# FlightControl.net
KiCad netlist of a schematic drawn in EAGLE
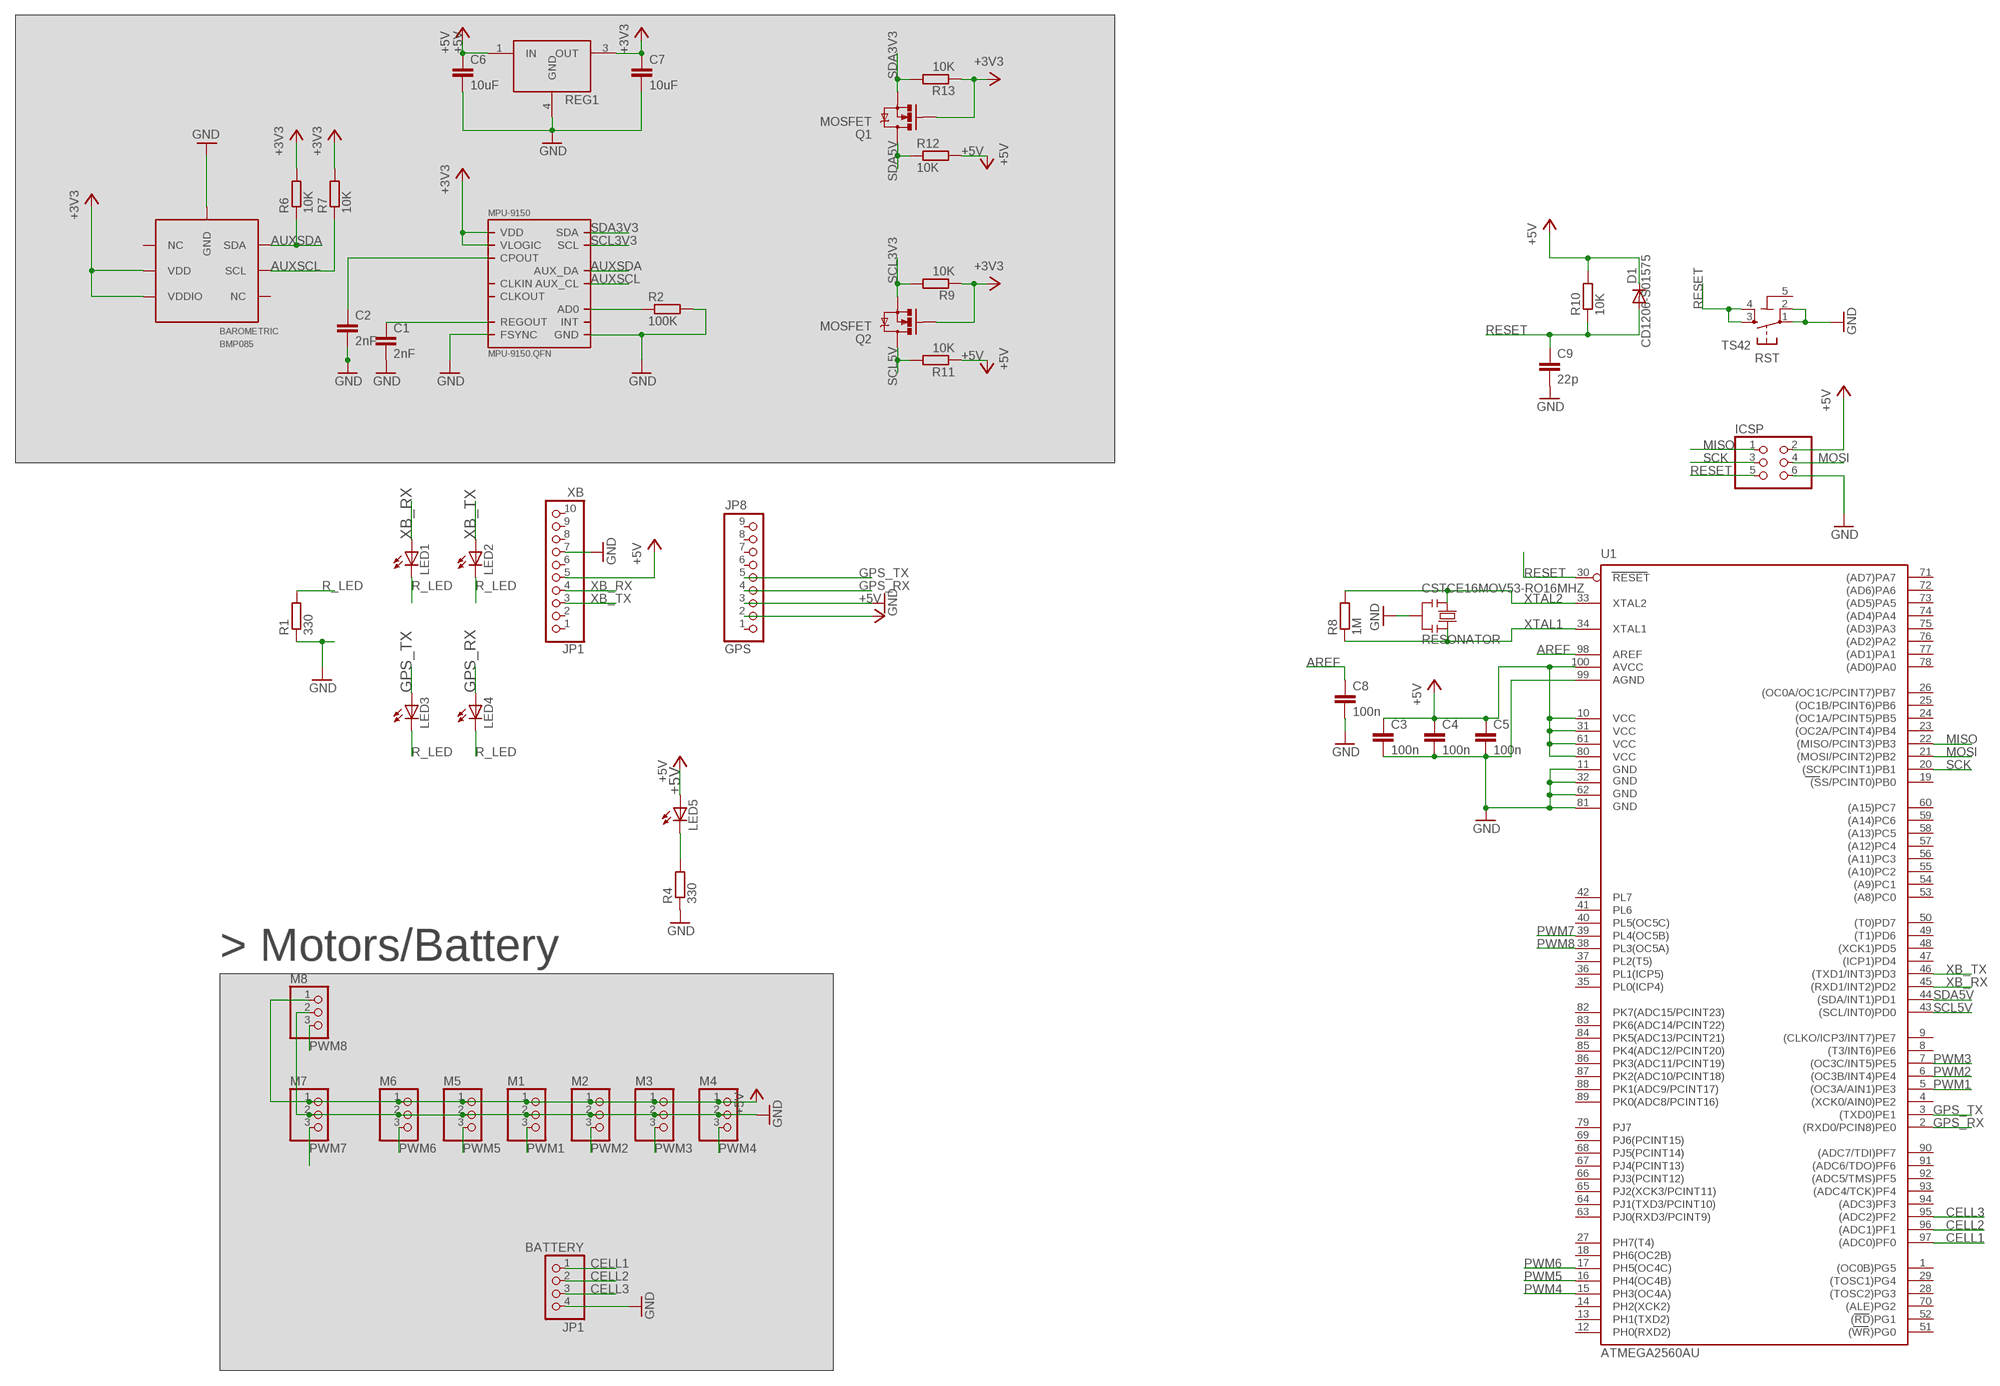
[diagram p0: schematic, sheet 1]

(export (version "E")
  (design (tool "Eeschema 10.0.6"))
  (components
    (comp (ref "BAROMETRIC")
      (value "BMP085")
      (footprint "eagle-import:7LGA")
      (libsource (lib "eagle-import") (part "BMP085"))
    )
    (comp (ref "BATTERY")
      (value "JP1")
      (footprint "eagle-import:1X04")
      (libsource (lib "eagle-import") (part "PINHD-1X4"))
    )
    (comp (ref "C1")
      (value "2nF")
      (footprint "eagle-import:C0603-ROUND")
      (libsource (lib "eagle-import") (part "C-EUC0603"))
    )
    (comp (ref "C2")
      (value "2nF")
      (footprint "eagle-import:C0603-ROUND")
      (libsource (lib "eagle-import") (part "C-EUC0603"))
    )
    (comp (ref "C3")
      (value "100n")
      (footprint "eagle-import:C0603-ROUND")
      (libsource (lib "eagle-import") (part "C-EU0603-RND"))
    )
    (comp (ref "C4")
      (value "100n")
      (footprint "eagle-import:C0603-ROUND")
      (libsource (lib "eagle-import") (part "C-EU0603-RND"))
    )
    (comp (ref "C5")
      (value "100n")
      (footprint "eagle-import:C0603-ROUND")
      (libsource (lib "eagle-import") (part "C-EU0603-RND"))
    )
    (comp (ref "C6")
      (value "10uF")
      (footprint "eagle-import:CAP-PTH-SMALLEZ")
      (libsource (lib "eagle-import") (part "CAPEZ"))
    )
    (comp (ref "C7")
      (value "10uF")
      (footprint "eagle-import:CAP-PTH-SMALLEZ")
      (libsource (lib "eagle-import") (part "CAPEZ"))
    )
    (comp (ref "C8")
      (value "100n")
      (footprint "eagle-import:C0603-ROUND")
      (libsource (lib "eagle-import") (part "C-EU0603-RND"))
    )
    (comp (ref "C9")
      (value "22p")
      (footprint "eagle-import:C0603-ROUND")
      (libsource (lib "eagle-import") (part "C-EU0603-RND"))
    )
    (comp (ref "CSTCE16MOV53-RO16MHZ")
      (value "RESONATOR")
      (footprint "eagle-import:RESONATOR")
      (libsource (lib "eagle-import") (part "RESONATORMU"))
    )
    (comp (ref "D1")
      (value "CD1206-S01575")
      (footprint "eagle-import:MINIMELF")
      (libsource (lib "eagle-import") (part "DIODE-MINIMELF"))
    )
    (comp (ref "GPS")
      (value "JP8")
      (footprint "eagle-import:1X09")
      (libsource (lib "eagle-import") (part "PINHD-1X9"))
    )
    (comp (ref "ICSP")
      (value "PINHD-2X3")
      (footprint "eagle-import:2X03")
      (libsource (lib "eagle-import") (part "PINHD-2X3"))
    )
    (comp (ref "JP1")
      (value "XB")
      (footprint "eagle-import:1X10")
      (libsource (lib "eagle-import") (part "PINHD-1X10_ARD"))
    )
    (comp (ref "LED1")
      (value "LEDCHIPLED_1206")
      (footprint "eagle-import:CHIPLED_1206")
      (libsource (lib "eagle-import") (part "LEDCHIPLED_1206"))
    )
    (comp (ref "LED2")
      (value "LEDCHIPLED_1206")
      (footprint "eagle-import:CHIPLED_1206")
      (libsource (lib "eagle-import") (part "LEDCHIPLED_1206"))
    )
    (comp (ref "LED3")
      (value "LEDCHIPLED_1206")
      (footprint "eagle-import:CHIPLED_1206")
      (libsource (lib "eagle-import") (part "LEDCHIPLED_1206"))
    )
    (comp (ref "LED4")
      (value "LEDCHIPLED_1206")
      (footprint "eagle-import:CHIPLED_1206")
      (libsource (lib "eagle-import") (part "LEDCHIPLED_1206"))
    )
    (comp (ref "LED5")
      (value "LEDCHIPLED_1206")
      (footprint "eagle-import:CHIPLED_1206")
      (libsource (lib "eagle-import") (part "LEDCHIPLED_1206"))
    )
    (comp (ref "M1")
      (value "PINHD-1X3")
      (footprint "eagle-import:1X03")
      (libsource (lib "eagle-import") (part "PINHD-1X3"))
    )
    (comp (ref "M2")
      (value "PINHD-1X3")
      (footprint "eagle-import:1X03")
      (libsource (lib "eagle-import") (part "PINHD-1X3"))
    )
    (comp (ref "M3")
      (value "PINHD-1X3")
      (footprint "eagle-import:1X03")
      (libsource (lib "eagle-import") (part "PINHD-1X3"))
    )
    (comp (ref "M4")
      (value "PINHD-1X3")
      (footprint "eagle-import:1X03")
      (libsource (lib "eagle-import") (part "PINHD-1X3"))
    )
    (comp (ref "M5")
      (value "PINHD-1X3")
      (footprint "eagle-import:1X03")
      (libsource (lib "eagle-import") (part "PINHD-1X3"))
    )
    (comp (ref "M6")
      (value "PINHD-1X3")
      (footprint "eagle-import:1X03")
      (libsource (lib "eagle-import") (part "PINHD-1X3"))
    )
    (comp (ref "M7")
      (value "PINHD-1X3")
      (footprint "eagle-import:1X03")
      (libsource (lib "eagle-import") (part "PINHD-1X3"))
    )
    (comp (ref "M8")
      (value "PINHD-1X3")
      (footprint "eagle-import:1X03")
      (libsource (lib "eagle-import") (part "PINHD-1X3"))
    )
    (comp (ref "MPU-9150")
      (value "MPU-9150.QFN")
      (footprint "eagle-import:QFN.24.4X4")
      (libsource (lib "eagle-import") (part "MPU-9150.QFN"))
    )
    (comp (ref "Q1")
      (value "MOSFET")
      (footprint "eagle-import:SOT23")
      (libsource (lib "eagle-import") (part "MOSFET-NCHANNELBSS138"))
    )
    (comp (ref "Q2")
      (value "MOSFET")
      (footprint "eagle-import:SOT23")
      (libsource (lib "eagle-import") (part "MOSFET-NCHANNELBSS138"))
    )
    (comp (ref "R1")
      (value "330")
      (footprint "eagle-import:R0603-ROUND")
      (libsource (lib "eagle-import") (part "R-EU_0603-RND"))
    )
    (comp (ref "R2")
      (value "100K")
      (footprint "eagle-import:R0603-ROUND")
      (libsource (lib "eagle-import") (part "R-EU_0603-RND"))
    )
    (comp (ref "R4")
      (value "330")
      (footprint "eagle-import:R0603-ROUND")
      (libsource (lib "eagle-import") (part "R-EU_0603-RND"))
    )
    (comp (ref "R6")
      (value "10K")
      (footprint "eagle-import:R0603-ROUND")
      (libsource (lib "eagle-import") (part "R-EU_0603-RND"))
    )
    (comp (ref "R7")
      (value "10K")
      (footprint "eagle-import:R0603-ROUND")
      (libsource (lib "eagle-import") (part "R-EU_0603-RND"))
    )
    (comp (ref "R8")
      (value "1M")
      (footprint "eagle-import:R0603-ROUND")
      (libsource (lib "eagle-import") (part "R-EU_R0603"))
    )
    (comp (ref "R9")
      (value "10K")
      (footprint "eagle-import:R0603-ROUND")
      (libsource (lib "eagle-import") (part "R-EU_R0603"))
    )
    (comp (ref "R10")
      (value "10K")
      (footprint "eagle-import:R0603-ROUND")
      (libsource (lib "eagle-import") (part "R-EU_R0603"))
    )
    (comp (ref "R11")
      (value "10K")
      (footprint "eagle-import:R0603-ROUND")
      (libsource (lib "eagle-import") (part "R-EU_R0603"))
    )
    (comp (ref "R12")
      (value "10K")
      (footprint "eagle-import:R0603-ROUND")
      (libsource (lib "eagle-import") (part "R-EU_R0603"))
    )
    (comp (ref "R13")
      (value "10K")
      (footprint "eagle-import:R0603-ROUND")
      (libsource (lib "eagle-import") (part "R-EU_R0603"))
    )
    (comp (ref "REG1")
      (value "LD39300")
      (footprint "eagle-import:DPAK")
      (libsource (lib "eagle-import") (part "LD39300"))
    )
    (comp (ref "RST")
      (value "TS42")
      (footprint "eagle-import:TS42")
      (libsource (lib "eagle-import") (part "TS42"))
    )
    (comp (ref "U1")
      (value "ATMEGA2560AU")
      (footprint "eagle-import:TQFP100")
      (libsource (lib "eagle-import") (part "ATMEGA2560AU"))
    )
  )
  (nets
    (net (code "1") (name "+3V3") (class "Default")
      (node (ref "BAROMETRIC") (pin "2") (pinfunction "VDD_2") (pintype "bidirectional"))
      (node (ref "BAROMETRIC") (pin "3") (pinfunction "VDDIO_3") (pintype "bidirectional"))
      (node (ref "C7") (pin "1") (pinfunction "1_1") (pintype "passive"))
      (node (ref "MPU-9150") (pin "13") (pinfunction "VDD_13") (pintype "bidirectional"))
      (node (ref "MPU-9150") (pin "3") (pinfunction "VDD_3") (pintype "bidirectional"))
      (node (ref "MPU-9150") (pin "8") (pinfunction "VLOGIC_8") (pintype "bidirectional"))
      (node (ref "Q1") (pin "1") (pinfunction "G_1") (pintype "passive"))
      (node (ref "Q2") (pin "1") (pinfunction "G_1") (pintype "passive"))
      (node (ref "R13") (pin "1") (pinfunction "1_1") (pintype "passive"))
      (node (ref "R6") (pin "2") (pinfunction "2_2") (pintype "passive"))
      (node (ref "R7") (pin "2") (pinfunction "2_2") (pintype "passive"))
      (node (ref "R9") (pin "1") (pinfunction "1_1") (pintype "passive"))
      (node (ref "REG1") (pin "3") (pinfunction "OUT_3") (pintype "bidirectional"))
    )
    (net (code "2") (name "+5V") (class "Default")
      (node (ref "C3") (pin "1") (pinfunction "1_1") (pintype "passive"))
      (node (ref "C4") (pin "1") (pinfunction "1_1") (pintype "passive"))
      (node (ref "C5") (pin "1") (pinfunction "1_1") (pintype "passive"))
      (node (ref "C6") (pin "1") (pinfunction "1_1") (pintype "passive"))
      (node (ref "D1") (pin "C") (pinfunction "C_C") (pintype "passive"))
      (node (ref "GPS") (pin "2") (pinfunction "2_2") (pintype "passive"))
      (node (ref "ICSP") (pin "2") (pinfunction "2_2") (pintype "passive"))
      (node (ref "JP1") (pin "5") (pinfunction "5_5") (pintype "passive"))
      (node (ref "LED5") (pin "A") (pinfunction "A_A") (pintype "passive"))
      (node (ref "M1") (pin "1") (pinfunction "1_1") (pintype "passive"))
      (node (ref "M2") (pin "1") (pinfunction "1_1") (pintype "passive"))
      (node (ref "M3") (pin "1") (pinfunction "1_1") (pintype "passive"))
      (node (ref "M4") (pin "1") (pinfunction "1_1") (pintype "passive"))
      (node (ref "M5") (pin "1") (pinfunction "1_1") (pintype "passive"))
      (node (ref "M6") (pin "1") (pinfunction "1_1") (pintype "passive"))
      (node (ref "M7") (pin "1") (pinfunction "1_1") (pintype "passive"))
      (node (ref "M8") (pin "1") (pinfunction "1_1") (pintype "passive"))
      (node (ref "R10") (pin "2") (pinfunction "2_2") (pintype "passive"))
      (node (ref "R11") (pin "1") (pinfunction "1_1") (pintype "passive"))
      (node (ref "R12") (pin "2") (pinfunction "2_2") (pintype "passive"))
      (node (ref "REG1") (pin "1") (pinfunction "IN_1") (pintype "bidirectional"))
      (node (ref "U1") (pin "10") (pinfunction "VCC_10") (pintype "power_in"))
      (node (ref "U1") (pin "100") (pinfunction "AVCC_100") (pintype "power_in"))
      (node (ref "U1") (pin "31") (pinfunction "VCC1_31") (pintype "power_in"))
      (node (ref "U1") (pin "61") (pinfunction "VCC2_61") (pintype "power_in"))
      (node (ref "U1") (pin "80") (pinfunction "VCC3_80") (pintype "power_in"))
    )
    (net (code "3") (name "/5-GND") (class "Default")
      (node (ref "RST") (pin "5") (pinfunction "5-GND_5") (pintype "power_in"))
    )
    (net (code "4") (name "/AREF") (class "Default")
      (node (ref "C8") (pin "1") (pinfunction "1_1") (pintype "passive"))
      (node (ref "U1") (pin "98") (pinfunction "AREF_98") (pintype "bidirectional"))
    )
    (net (code "5") (name "/AUXSCL") (class "Default")
      (node (ref "BAROMETRIC") (pin "5") (pinfunction "SCL_5") (pintype "bidirectional"))
      (node (ref "MPU-9150") (pin "7") (pinfunction "AUX_CL_7") (pintype "bidirectional"))
      (node (ref "R7") (pin "1") (pinfunction "1_1") (pintype "passive"))
    )
    (net (code "6") (name "/AUXSDA") (class "Default")
      (node (ref "BAROMETRIC") (pin "6") (pinfunction "SDA_6") (pintype "bidirectional"))
      (node (ref "MPU-9150") (pin "6") (pinfunction "AUX_DA_6") (pintype "bidirectional"))
      (node (ref "R6") (pin "1") (pinfunction "1_1") (pintype "passive"))
    )
    (net (code "7") (name "/CELL1") (class "Default")
      (node (ref "BATTERY") (pin "1") (pinfunction "1_1") (pintype "passive"))
      (node (ref "U1") (pin "97") (pinfunction "(ADC0)PF0_97") (pintype "bidirectional"))
    )
    (net (code "8") (name "/CELL2") (class "Default")
      (node (ref "BATTERY") (pin "2") (pinfunction "2_2") (pintype "passive"))
      (node (ref "U1") (pin "96") (pinfunction "(ADC1)PF1_96") (pintype "bidirectional"))
    )
    (net (code "9") (name "/CELL3") (class "Default")
      (node (ref "BATTERY") (pin "3") (pinfunction "3_3") (pintype "passive"))
      (node (ref "U1") (pin "95") (pinfunction "(ADC2)PF2_95") (pintype "bidirectional"))
    )
    (net (code "10") (name "/GPS_RX") (class "Default")
      (node (ref "GPS") (pin "4") (pinfunction "4_4") (pintype "passive"))
      (node (ref "LED4") (pin "A") (pinfunction "A_A") (pintype "passive"))
      (node (ref "U1") (pin "2") (pinfunction "(RXD0/PCIN8)PE0_2") (pintype "bidirectional"))
    )
    (net (code "11") (name "/GPS_TX") (class "Default")
      (node (ref "GPS") (pin "5") (pinfunction "5_5") (pintype "passive"))
      (node (ref "LED3") (pin "A") (pinfunction "A_A") (pintype "passive"))
      (node (ref "U1") (pin "3") (pinfunction "(TXD0)PE1_3") (pintype "bidirectional"))
    )
    (net (code "12") (name "/MISO") (class "Default")
      (node (ref "ICSP") (pin "1") (pinfunction "1_1") (pintype "passive"))
      (node (ref "U1") (pin "22") (pinfunction "(MISO/PCINT3)PB3_22") (pintype "bidirectional"))
    )
    (net (code "13") (name "/MOSI") (class "Default")
      (node (ref "ICSP") (pin "4") (pinfunction "4_4") (pintype "passive"))
      (node (ref "U1") (pin "21") (pinfunction "(MOSI/PCINT2)PB2_21") (pintype "bidirectional"))
    )
    (net (code "14") (name "/PWM1") (class "Default")
      (node (ref "M1") (pin "3") (pinfunction "3_3") (pintype "passive"))
      (node (ref "U1") (pin "5") (pinfunction "(OC3A/AIN1)PE3_5") (pintype "bidirectional"))
    )
    (net (code "15") (name "/PWM2") (class "Default")
      (node (ref "M2") (pin "3") (pinfunction "3_3") (pintype "passive"))
      (node (ref "U1") (pin "6") (pinfunction "(OC3B/INT4)PE4_6") (pintype "bidirectional"))
    )
    (net (code "16") (name "/PWM3") (class "Default")
      (node (ref "M3") (pin "3") (pinfunction "3_3") (pintype "passive"))
      (node (ref "U1") (pin "7") (pinfunction "(OC3C/INT5)PE5_7") (pintype "bidirectional"))
    )
    (net (code "17") (name "/PWM4") (class "Default")
      (node (ref "M4") (pin "3") (pinfunction "3_3") (pintype "passive"))
      (node (ref "U1") (pin "15") (pinfunction "PH3(OC4A)_15") (pintype "bidirectional"))
    )
    (net (code "18") (name "/PWM5") (class "Default")
      (node (ref "M5") (pin "3") (pinfunction "3_3") (pintype "passive"))
      (node (ref "U1") (pin "16") (pinfunction "PH4(OC4B)_16") (pintype "bidirectional"))
    )
    (net (code "19") (name "/PWM6") (class "Default")
      (node (ref "M6") (pin "3") (pinfunction "3_3") (pintype "passive"))
      (node (ref "U1") (pin "17") (pinfunction "PH5(OC4C)_17") (pintype "bidirectional"))
    )
    (net (code "20") (name "/PWM7") (class "Default")
      (node (ref "M7") (pin "3") (pinfunction "3_3") (pintype "passive"))
      (node (ref "U1") (pin "39") (pinfunction "PL4(OC5B)_39") (pintype "bidirectional"))
    )
    (net (code "21") (name "/PWM8") (class "Default")
      (node (ref "M8") (pin "3") (pinfunction "3_3") (pintype "passive"))
      (node (ref "U1") (pin "38") (pinfunction "PL3(OC5A)_38") (pintype "bidirectional"))
    )
    (net (code "22") (name "/RESET") (class "Default")
      (node (ref "C9") (pin "1") (pinfunction "1_1") (pintype "passive"))
      (node (ref "D1") (pin "A") (pinfunction "A_A") (pintype "passive"))
      (node (ref "ICSP") (pin "5") (pinfunction "5_5") (pintype "passive"))
      (node (ref "R10") (pin "1") (pinfunction "1_1") (pintype "passive"))
      (node (ref "RST") (pin "3") (pinfunction "3_3") (pintype "passive"))
      (node (ref "RST") (pin "4") (pinfunction "4_4") (pintype "passive"))
      (node (ref "U1") (pin "30") (pinfunction "RESET_30") (pintype "input"))
    )
    (net (code "23") (name "/R_LED") (class "Default")
      (node (ref "LED1") (pin "C") (pinfunction "C_C") (pintype "passive"))
      (node (ref "LED2") (pin "C") (pinfunction "C_C") (pintype "passive"))
      (node (ref "LED3") (pin "C") (pinfunction "C_C") (pintype "passive"))
      (node (ref "LED4") (pin "C") (pinfunction "C_C") (pintype "passive"))
      (node (ref "R1") (pin "2") (pinfunction "2_2") (pintype "passive"))
    )
    (net (code "24") (name "/SCK") (class "Default")
      (node (ref "ICSP") (pin "3") (pinfunction "3_3") (pintype "passive"))
      (node (ref "U1") (pin "20") (pinfunction "(SCK/PCINT1)PB1_20") (pintype "bidirectional"))
    )
    (net (code "25") (name "/SCL3V3") (class "Default")
      (node (ref "MPU-9150") (pin "23") (pinfunction "SCL_23") (pintype "bidirectional"))
      (node (ref "Q2") (pin "2") (pinfunction "S_2") (pintype "passive"))
      (node (ref "R9") (pin "2") (pinfunction "2_2") (pintype "passive"))
    )
    (net (code "26") (name "/SCL5V") (class "Default")
      (node (ref "Q2") (pin "3") (pinfunction "D_3") (pintype "passive"))
      (node (ref "R11") (pin "2") (pinfunction "2_2") (pintype "passive"))
      (node (ref "U1") (pin "43") (pinfunction "(SCL/INT0)PD0_43") (pintype "bidirectional"))
    )
    (net (code "27") (name "/SDA3V3") (class "Default")
      (node (ref "MPU-9150") (pin "24") (pinfunction "SDA_24") (pintype "bidirectional"))
      (node (ref "Q1") (pin "2") (pinfunction "S_2") (pintype "passive"))
      (node (ref "R13") (pin "2") (pinfunction "2_2") (pintype "passive"))
    )
    (net (code "28") (name "/SDA5V") (class "Default")
      (node (ref "Q1") (pin "3") (pinfunction "D_3") (pintype "passive"))
      (node (ref "R12") (pin "1") (pinfunction "1_1") (pintype "passive"))
      (node (ref "U1") (pin "44") (pinfunction "(SDA/INT1)PD1_44") (pintype "bidirectional"))
    )
    (net (code "29") (name "/XB_RX") (class "Default")
      (node (ref "JP1") (pin "4") (pinfunction "4_4") (pintype "passive"))
      (node (ref "LED1") (pin "A") (pinfunction "A_A") (pintype "passive"))
      (node (ref "U1") (pin "45") (pinfunction "(RXD1/INT2)PD2_45") (pintype "bidirectional"))
    )
    (net (code "30") (name "/XB_TX") (class "Default")
      (node (ref "JP1") (pin "3") (pinfunction "3_3") (pintype "passive"))
      (node (ref "LED2") (pin "A") (pinfunction "A_A") (pintype "passive"))
      (node (ref "U1") (pin "46") (pinfunction "(TXD1/INT3)PD3_46") (pintype "bidirectional"))
    )
    (net (code "31") (name "/XTAL1") (class "Default")
      (node (ref "CSTCE16MOV53-RO16MHZ") (pin "3") (pinfunction "3_3") (pintype "passive"))
      (node (ref "R8") (pin "1") (pinfunction "1_1") (pintype "passive"))
      (node (ref "U1") (pin "34") (pinfunction "XTAL1_34") (pintype "input"))
    )
    (net (code "32") (name "/XTAL2") (class "Default")
      (node (ref "CSTCE16MOV53-RO16MHZ") (pin "1") (pinfunction "1_1") (pintype "passive"))
      (node (ref "R8") (pin "2") (pinfunction "2_2") (pintype "passive"))
      (node (ref "U1") (pin "33") (pinfunction "XTAL2_33") (pintype "output"))
    )
    (net (code "33") (name "GND") (class "Default")
      (node (ref "BAROMETRIC") (pin "7") (pinfunction "GND_7") (pintype "bidirectional"))
      (node (ref "BATTERY") (pin "4") (pinfunction "4_4") (pintype "passive"))
      (node (ref "C1") (pin "2") (pinfunction "2_2") (pintype "passive"))
      (node (ref "C2") (pin "2") (pinfunction "2_2") (pintype "passive"))
      (node (ref "C3") (pin "2") (pinfunction "2_2") (pintype "passive"))
      (node (ref "C4") (pin "2") (pinfunction "2_2") (pintype "passive"))
      (node (ref "C5") (pin "2") (pinfunction "2_2") (pintype "passive"))
      (node (ref "C6") (pin "2") (pinfunction "2_2") (pintype "passive"))
      (node (ref "C7") (pin "2") (pinfunction "2_2") (pintype "passive"))
      (node (ref "C8") (pin "2") (pinfunction "2_2") (pintype "passive"))
      (node (ref "C9") (pin "2") (pinfunction "2_2") (pintype "passive"))
      (node (ref "CSTCE16MOV53-RO16MHZ") (pin "2") (pinfunction "2_2") (pintype "passive"))
      (node (ref "GPS") (pin "3") (pinfunction "3_3") (pintype "passive"))
      (node (ref "ICSP") (pin "6") (pinfunction "6_6") (pintype "passive"))
      (node (ref "JP1") (pin "7") (pinfunction "7_7") (pintype "passive"))
      (node (ref "M1") (pin "2") (pinfunction "2_2") (pintype "passive"))
      (node (ref "M2") (pin "2") (pinfunction "2_2") (pintype "passive"))
      (node (ref "M3") (pin "2") (pinfunction "2_2") (pintype "passive"))
      (node (ref "M4") (pin "2") (pinfunction "2_2") (pintype "passive"))
      (node (ref "M5") (pin "2") (pinfunction "2_2") (pintype "passive"))
      (node (ref "M6") (pin "2") (pinfunction "2_2") (pintype "passive"))
      (node (ref "M7") (pin "2") (pinfunction "2_2") (pintype "passive"))
      (node (ref "M8") (pin "2") (pinfunction "2_2") (pintype "passive"))
      (node (ref "MPU-9150") (pin "11") (pinfunction "FSYNC_11") (pintype "bidirectional"))
      (node (ref "MPU-9150") (pin "15") (pinfunction "GND_15") (pintype "bidirectional"))
      (node (ref "MPU-9150") (pin "17") (pinfunction "GND_17") (pintype "bidirectional"))
      (node (ref "MPU-9150") (pin "18") (pinfunction "GND_18") (pintype "bidirectional"))
      (node (ref "R1") (pin "1") (pinfunction "1_1") (pintype "passive"))
      (node (ref "R2") (pin "2") (pinfunction "2_2") (pintype "passive"))
      (node (ref "R4") (pin "1") (pinfunction "1_1") (pintype "passive"))
      (node (ref "REG1") (pin "4") (pinfunction "GND_4") (pintype "bidirectional"))
      (node (ref "RST") (pin "1") (pinfunction "1_1") (pintype "passive"))
      (node (ref "RST") (pin "2") (pinfunction "2_2") (pintype "passive"))
      (node (ref "U1") (pin "11") (pinfunction "GND_11") (pintype "power_in"))
      (node (ref "U1") (pin "32") (pinfunction "GND1_32") (pintype "power_in"))
      (node (ref "U1") (pin "62") (pinfunction "GND2_62") (pintype "power_in"))
      (node (ref "U1") (pin "81") (pinfunction "GND3_81") (pintype "power_in"))
      (node (ref "U1") (pin "99") (pinfunction "AGND_99") (pintype "power_in"))
    )
    (net (code "34") (name "Net-(LED5-PadC)") (class "Default")
      (node (ref "LED5") (pin "C") (pinfunction "C_C") (pintype "passive"))
      (node (ref "R4") (pin "2") (pinfunction "2_2") (pintype "passive"))
    )
    (net (code "35") (name "Net-(MPU-9150-AD0)") (class "Default")
      (node (ref "MPU-9150") (pin "9") (pinfunction "AD0_9") (pintype "bidirectional"))
      (node (ref "R2") (pin "1") (pinfunction "1_1") (pintype "passive"))
    )
    (net (code "36") (name "Net-(MPU-9150-CPOUT)") (class "Default")
      (node (ref "C2") (pin "1") (pinfunction "1_1") (pintype "passive"))
      (node (ref "MPU-9150") (pin "20") (pinfunction "CPOUT_20") (pintype "bidirectional"))
    )
    (net (code "37") (name "Net-(MPU-9150-REGOUT)") (class "Default")
      (node (ref "C1") (pin "1") (pinfunction "1_1") (pintype "passive"))
      (node (ref "MPU-9150") (pin "10") (pinfunction "REGOUT_10") (pintype "bidirectional"))
    )
    (net (code "38") (name "unconnected-(BAROMETRIC-NC-Pad1)") (class "Default")
      (node (ref "BAROMETRIC") (pin "1") (pinfunction "NC_1") (pintype "bidirectional"))
    )
    (net (code "39") (name "unconnected-(BAROMETRIC-NC-Pad4)") (class "Default")
      (node (ref "BAROMETRIC") (pin "4") (pinfunction "NC_4") (pintype "bidirectional"))
    )
    (net (code "40") (name "unconnected-(GPS-Pad1)") (class "Default")
      (node (ref "GPS") (pin "1") (pinfunction "1_1") (pintype "passive"))
    )
    (net (code "41") (name "unconnected-(GPS-Pad6)") (class "Default")
      (node (ref "GPS") (pin "6") (pinfunction "6_6") (pintype "passive"))
    )
    (net (code "42") (name "unconnected-(GPS-Pad7)") (class "Default")
      (node (ref "GPS") (pin "7") (pinfunction "7_7") (pintype "passive"))
    )
    (net (code "43") (name "unconnected-(GPS-Pad8)") (class "Default")
      (node (ref "GPS") (pin "8") (pinfunction "8_8") (pintype "passive"))
    )
    (net (code "44") (name "unconnected-(GPS-Pad9)") (class "Default")
      (node (ref "GPS") (pin "9") (pinfunction "9_9") (pintype "passive"))
    )
    (net (code "45") (name "unconnected-(JP1-Pad1)") (class "Default")
      (node (ref "JP1") (pin "1") (pinfunction "1_1") (pintype "passive"))
    )
    (net (code "46") (name "unconnected-(JP1-Pad2)") (class "Default")
      (node (ref "JP1") (pin "2") (pinfunction "2_2") (pintype "passive"))
    )
    (net (code "47") (name "unconnected-(JP1-Pad6)") (class "Default")
      (node (ref "JP1") (pin "6") (pinfunction "6_6") (pintype "passive"))
    )
    (net (code "48") (name "unconnected-(JP1-Pad8)") (class "Default")
      (node (ref "JP1") (pin "8") (pinfunction "8_8") (pintype "passive"))
    )
    (net (code "49") (name "unconnected-(JP1-Pad9)") (class "Default")
      (node (ref "JP1") (pin "9") (pinfunction "9_9") (pintype "passive"))
    )
    (net (code "50") (name "unconnected-(JP1-Pad10)") (class "Default")
      (node (ref "JP1") (pin "10") (pinfunction "10_10") (pintype "passive"))
    )
    (net (code "51") (name "unconnected-(MPU-9150-CLKIN-Pad1)") (class "Default")
      (node (ref "MPU-9150") (pin "1") (pinfunction "CLKIN_1") (pintype "bidirectional"))
    )
    (net (code "52") (name "unconnected-(MPU-9150-CLKOUT-Pad22)") (class "Default")
      (node (ref "MPU-9150") (pin "22") (pinfunction "CLKOUT_22") (pintype "bidirectional"))
    )
    (net (code "53") (name "unconnected-(MPU-9150-INT-Pad12)") (class "Default")
      (node (ref "MPU-9150") (pin "12") (pinfunction "INT_12") (pintype "bidirectional"))
    )
    (net (code "54") (name "unconnected-(U1-(A8)PC0-Pad53)") (class "Default")
      (node (ref "U1") (pin "53") (pinfunction "(A8)PC0_53") (pintype "bidirectional"))
    )
    (net (code "55") (name "unconnected-(U1-(A9)PC1-Pad54)") (class "Default")
      (node (ref "U1") (pin "54") (pinfunction "(A9)PC1_54") (pintype "bidirectional"))
    )
    (net (code "56") (name "unconnected-(U1-(A10)PC2-Pad55)") (class "Default")
      (node (ref "U1") (pin "55") (pinfunction "(A10)PC2_55") (pintype "bidirectional"))
    )
    (net (code "57") (name "unconnected-(U1-(A11)PC3-Pad56)") (class "Default")
      (node (ref "U1") (pin "56") (pinfunction "(A11)PC3_56") (pintype "bidirectional"))
    )
    (net (code "58") (name "unconnected-(U1-(A12)PC4-Pad57)") (class "Default")
      (node (ref "U1") (pin "57") (pinfunction "(A12)PC4_57") (pintype "bidirectional"))
    )
    (net (code "59") (name "unconnected-(U1-(A13)PC5-Pad58)") (class "Default")
      (node (ref "U1") (pin "58") (pinfunction "(A13)PC5_58") (pintype "bidirectional"))
    )
    (net (code "60") (name "unconnected-(U1-(A14)PC6-Pad59)") (class "Default")
      (node (ref "U1") (pin "59") (pinfunction "(A14)PC6_59") (pintype "bidirectional"))
    )
    (net (code "61") (name "unconnected-(U1-(A15)PC7-Pad60)") (class "Default")
      (node (ref "U1") (pin "60") (pinfunction "(A15)PC7_60") (pintype "bidirectional"))
    )
    (net (code "62") (name "unconnected-(U1-(AD0)PA0-Pad78)") (class "Default")
      (node (ref "U1") (pin "78") (pinfunction "(AD0)PA0_78") (pintype "bidirectional"))
    )
    (net (code "63") (name "unconnected-(U1-(AD1)PA1-Pad77)") (class "Default")
      (node (ref "U1") (pin "77") (pinfunction "(AD1)PA1_77") (pintype "bidirectional"))
    )
    (net (code "64") (name "unconnected-(U1-(AD2)PA2-Pad76)") (class "Default")
      (node (ref "U1") (pin "76") (pinfunction "(AD2)PA2_76") (pintype "bidirectional"))
    )
    (net (code "65") (name "unconnected-(U1-(AD3)PA3-Pad75)") (class "Default")
      (node (ref "U1") (pin "75") (pinfunction "(AD3)PA3_75") (pintype "bidirectional"))
    )
    (net (code "66") (name "unconnected-(U1-(AD4)PA4-Pad74)") (class "Default")
      (node (ref "U1") (pin "74") (pinfunction "(AD4)PA4_74") (pintype "bidirectional"))
    )
    (net (code "67") (name "unconnected-(U1-(AD5)PA5-Pad73)") (class "Default")
      (node (ref "U1") (pin "73") (pinfunction "(AD5)PA5_73") (pintype "bidirectional"))
    )
    (net (code "68") (name "unconnected-(U1-(AD6)PA6-Pad72)") (class "Default")
      (node (ref "U1") (pin "72") (pinfunction "(AD6)PA6_72") (pintype "bidirectional"))
    )
    (net (code "69") (name "unconnected-(U1-(AD7)PA7-Pad71)") (class "Default")
      (node (ref "U1") (pin "71") (pinfunction "(AD7)PA7_71") (pintype "bidirectional"))
    )
    (net (code "70") (name "unconnected-(U1-(ADC3)PF3-Pad94)") (class "Default")
      (node (ref "U1") (pin "94") (pinfunction "(ADC3)PF3_94") (pintype "bidirectional"))
    )
    (net (code "71") (name "unconnected-(U1-(ADC4{slash}TCK)PF4-Pad93)") (class "Default")
      (node (ref "U1") (pin "93") (pinfunction "(ADC4/TCK)PF4_93") (pintype "bidirectional"))
    )
    (net (code "72") (name "unconnected-(U1-(ADC5{slash}TMS)PF5-Pad92)") (class "Default")
      (node (ref "U1") (pin "92") (pinfunction "(ADC5/TMS)PF5_92") (pintype "bidirectional"))
    )
    (net (code "73") (name "unconnected-(U1-(ADC6{slash}TDO)PF6-Pad91)") (class "Default")
      (node (ref "U1") (pin "91") (pinfunction "(ADC6/TDO)PF6_91") (pintype "bidirectional"))
    )
    (net (code "74") (name "unconnected-(U1-(ADC7{slash}TDI)PF7-Pad90)") (class "Default")
      (node (ref "U1") (pin "90") (pinfunction "(ADC7/TDI)PF7_90") (pintype "bidirectional"))
    )
    (net (code "75") (name "unconnected-(U1-(ALE)PG2-Pad70)") (class "Default")
      (node (ref "U1") (pin "70") (pinfunction "(ALE)PG2_70") (pintype "bidirectional"))
    )
    (net (code "76") (name "unconnected-(U1-(CLKO{slash}ICP3{slash}INT7)PE7-Pad9)") (class "Default")
      (node (ref "U1") (pin "9") (pinfunction "(CLKO/ICP3/INT7)PE7_9") (pintype "bidirectional"))
    )
    (net (code "77") (name "unconnected-(U1-(ICP1)PD4-Pad47)") (class "Default")
      (node (ref "U1") (pin "47") (pinfunction "(ICP1)PD4_47") (pintype "bidirectional"))
    )
    (net (code "78") (name "unconnected-(U1-(OC0A{slash}OC1C{slash}PCINT7)PB7-Pad26)") (class "Default")
      (node (ref "U1") (pin "26") (pinfunction "(OC0A/OC1C/PCINT7)PB7_26") (pintype "bidirectional"))
    )
    (net (code "79") (name "unconnected-(U1-(OC0B)PG5-Pad1)") (class "Default")
      (node (ref "U1") (pin "1") (pinfunction "(OC0B)PG5_1") (pintype "bidirectional"))
    )
    (net (code "80") (name "unconnected-(U1-(OC1A{slash}PCINT5)PB5-Pad24)") (class "Default")
      (node (ref "U1") (pin "24") (pinfunction "(OC1A/PCINT5)PB5_24") (pintype "bidirectional"))
    )
    (net (code "81") (name "unconnected-(U1-(OC1B{slash}PCINT6)PB6-Pad25)") (class "Default")
      (node (ref "U1") (pin "25") (pinfunction "(OC1B/PCINT6)PB6_25") (pintype "bidirectional"))
    )
    (net (code "82") (name "unconnected-(U1-(OC2A{slash}PCINT4)PB4-Pad23)") (class "Default")
      (node (ref "U1") (pin "23") (pinfunction "(OC2A/PCINT4)PB4_23") (pintype "bidirectional"))
    )
    (net (code "83") (name "unconnected-(U1-(RD)PG1-Pad52)") (class "Default")
      (node (ref "U1") (pin "52") (pinfunction "(RD)PG1_52") (pintype "bidirectional"))
    )
    (net (code "84") (name "unconnected-(U1-(SS{slash}PCINT0)PB0-Pad19)") (class "Default")
      (node (ref "U1") (pin "19") (pinfunction "(SS/PCINT0)PB0_19") (pintype "bidirectional"))
    )
    (net (code "85") (name "unconnected-(U1-(T0)PD7-Pad50)") (class "Default")
      (node (ref "U1") (pin "50") (pinfunction "(T0)PD7_50") (pintype "bidirectional"))
    )
    (net (code "86") (name "unconnected-(U1-(T1)PD6-Pad49)") (class "Default")
      (node (ref "U1") (pin "49") (pinfunction "(T1)PD6_49") (pintype "bidirectional"))
    )
    (net (code "87") (name "unconnected-(U1-(T3{slash}INT6)PE6-Pad8)") (class "Default")
      (node (ref "U1") (pin "8") (pinfunction "(T3/INT6)PE6_8") (pintype "bidirectional"))
    )
    (net (code "88") (name "unconnected-(U1-(TOSC1)PG4-Pad29)") (class "Default")
      (node (ref "U1") (pin "29") (pinfunction "(TOSC1)PG4_29") (pintype "bidirectional"))
    )
    (net (code "89") (name "unconnected-(U1-(TOSC2)PG3-Pad28)") (class "Default")
      (node (ref "U1") (pin "28") (pinfunction "(TOSC2)PG3_28") (pintype "bidirectional"))
    )
    (net (code "90") (name "unconnected-(U1-(WR)PG0-Pad51)") (class "Default")
      (node (ref "U1") (pin "51") (pinfunction "(WR)PG0_51") (pintype "bidirectional"))
    )
    (net (code "91") (name "unconnected-(U1-(XCK0{slash}AIN0)PE2-Pad4)") (class "Default")
      (node (ref "U1") (pin "4") (pinfunction "(XCK0/AIN0)PE2_4") (pintype "bidirectional"))
    )
    (net (code "92") (name "unconnected-(U1-(XCK1)PD5-Pad48)") (class "Default")
      (node (ref "U1") (pin "48") (pinfunction "(XCK1)PD5_48") (pintype "bidirectional"))
    )
    (net (code "93") (name "unconnected-(U1-PH0(RXD2)-Pad12)") (class "Default")
      (node (ref "U1") (pin "12") (pinfunction "PH0(RXD2)_12") (pintype "bidirectional"))
    )
    (net (code "94") (name "unconnected-(U1-PH1(TXD2)-Pad13)") (class "Default")
      (node (ref "U1") (pin "13") (pinfunction "PH1(TXD2)_13") (pintype "bidirectional"))
    )
    (net (code "95") (name "unconnected-(U1-PH2(XCK2)-Pad14)") (class "Default")
      (node (ref "U1") (pin "14") (pinfunction "PH2(XCK2)_14") (pintype "bidirectional"))
    )
    (net (code "96") (name "unconnected-(U1-PH6(OC2B)-Pad18)") (class "Default")
      (node (ref "U1") (pin "18") (pinfunction "PH6(OC2B)_18") (pintype "bidirectional"))
    )
    (net (code "97") (name "unconnected-(U1-PH7(T4)-Pad27)") (class "Default")
      (node (ref "U1") (pin "27") (pinfunction "PH7(T4)_27") (pintype "bidirectional"))
    )
    (net (code "98") (name "unconnected-(U1-PJ0(RXD3{slash}PCINT9)-Pad63)") (class "Default")
      (node (ref "U1") (pin "63") (pinfunction "PJ0(RXD3/PCINT9)_63") (pintype "bidirectional"))
    )
    (net (code "99") (name "unconnected-(U1-PJ1(TXD3{slash}PCINT10)-Pad64)") (class "Default")
      (node (ref "U1") (pin "64") (pinfunction "PJ1(TXD3/PCINT10)_64") (pintype "bidirectional"))
    )
    (net (code "100") (name "unconnected-(U1-PJ2(XCK3{slash}PCINT11)-Pad65)") (class "Default")
      (node (ref "U1") (pin "65") (pinfunction "PJ2(XCK3/PCINT11)_65") (pintype "bidirectional"))
    )
    (net (code "101") (name "unconnected-(U1-PJ3(PCINT12)-Pad66)") (class "Default")
      (node (ref "U1") (pin "66") (pinfunction "PJ3(PCINT12)_66") (pintype "bidirectional"))
    )
    (net (code "102") (name "unconnected-(U1-PJ4(PCINT13)-Pad67)") (class "Default")
      (node (ref "U1") (pin "67") (pinfunction "PJ4(PCINT13)_67") (pintype "bidirectional"))
    )
    (net (code "103") (name "unconnected-(U1-PJ5(PCINT14)-Pad68)") (class "Default")
      (node (ref "U1") (pin "68") (pinfunction "PJ5(PCINT14)_68") (pintype "bidirectional"))
    )
    (net (code "104") (name "unconnected-(U1-PJ6(PCINT15)-Pad69)") (class "Default")
      (node (ref "U1") (pin "69") (pinfunction "PJ6(PCINT15)_69") (pintype "bidirectional"))
    )
    (net (code "105") (name "unconnected-(U1-PJ7-Pad79)") (class "Default")
      (node (ref "U1") (pin "79") (pinfunction "PJ7_79") (pintype "bidirectional"))
    )
    (net (code "106") (name "unconnected-(U1-PK0(ADC8{slash}PCINT16)-Pad89)") (class "Default")
      (node (ref "U1") (pin "89") (pinfunction "PK0(ADC8/PCINT16)_89") (pintype "bidirectional"))
    )
    (net (code "107") (name "unconnected-(U1-PK1(ADC9{slash}PCINT17)-Pad88)") (class "Default")
      (node (ref "U1") (pin "88") (pinfunction "PK1(ADC9/PCINT17)_88") (pintype "bidirectional"))
    )
    (net (code "108") (name "unconnected-(U1-PK2(ADC10{slash}PCINT18)-Pad87)") (class "Default")
      (node (ref "U1") (pin "87") (pinfunction "PK2(ADC10/PCINT18)_87") (pintype "bidirectional"))
    )
    (net (code "109") (name "unconnected-(U1-PK3(ADC11{slash}PCINT19)-Pad86)") (class "Default")
      (node (ref "U1") (pin "86") (pinfunction "PK3(ADC11/PCINT19)_86") (pintype "bidirectional"))
    )
    (net (code "110") (name "unconnected-(U1-PK4(ADC12{slash}PCINT20)-Pad85)") (class "Default")
      (node (ref "U1") (pin "85") (pinfunction "PK4(ADC12/PCINT20)_85") (pintype "bidirectional"))
    )
    (net (code "111") (name "unconnected-(U1-PK5(ADC13{slash}PCINT21)-Pad84)") (class "Default")
      (node (ref "U1") (pin "84") (pinfunction "PK5(ADC13/PCINT21)_84") (pintype "bidirectional"))
    )
    (net (code "112") (name "unconnected-(U1-PK6(ADC14{slash}PCINT22)-Pad83)") (class "Default")
      (node (ref "U1") (pin "83") (pinfunction "PK6(ADC14/PCINT22)_83") (pintype "bidirectional"))
    )
    (net (code "113") (name "unconnected-(U1-PK7(ADC15{slash}PCINT23)-Pad82)") (class "Default")
      (node (ref "U1") (pin "82") (pinfunction "PK7(ADC15/PCINT23)_82") (pintype "bidirectional"))
    )
    (net (code "114") (name "unconnected-(U1-PL0(ICP4)-Pad35)") (class "Default")
      (node (ref "U1") (pin "35") (pinfunction "PL0(ICP4)_35") (pintype "bidirectional"))
    )
    (net (code "115") (name "unconnected-(U1-PL1(ICP5)-Pad36)") (class "Default")
      (node (ref "U1") (pin "36") (pinfunction "PL1(ICP5)_36") (pintype "bidirectional"))
    )
    (net (code "116") (name "unconnected-(U1-PL2(T5)-Pad37)") (class "Default")
      (node (ref "U1") (pin "37") (pinfunction "PL2(T5)_37") (pintype "bidirectional"))
    )
    (net (code "117") (name "unconnected-(U1-PL5(OC5C)-Pad40)") (class "Default")
      (node (ref "U1") (pin "40") (pinfunction "PL5(OC5C)_40") (pintype "bidirectional"))
    )
    (net (code "118") (name "unconnected-(U1-PL6-Pad41)") (class "Default")
      (node (ref "U1") (pin "41") (pinfunction "PL6_41") (pintype "bidirectional"))
    )
    (net (code "119") (name "unconnected-(U1-PL7-Pad42)") (class "Default")
      (node (ref "U1") (pin "42") (pinfunction "PL7_42") (pintype "bidirectional"))
    )
  )
)
